# battery.net
KiCad netlist of a schematic drawn in Altium Designer
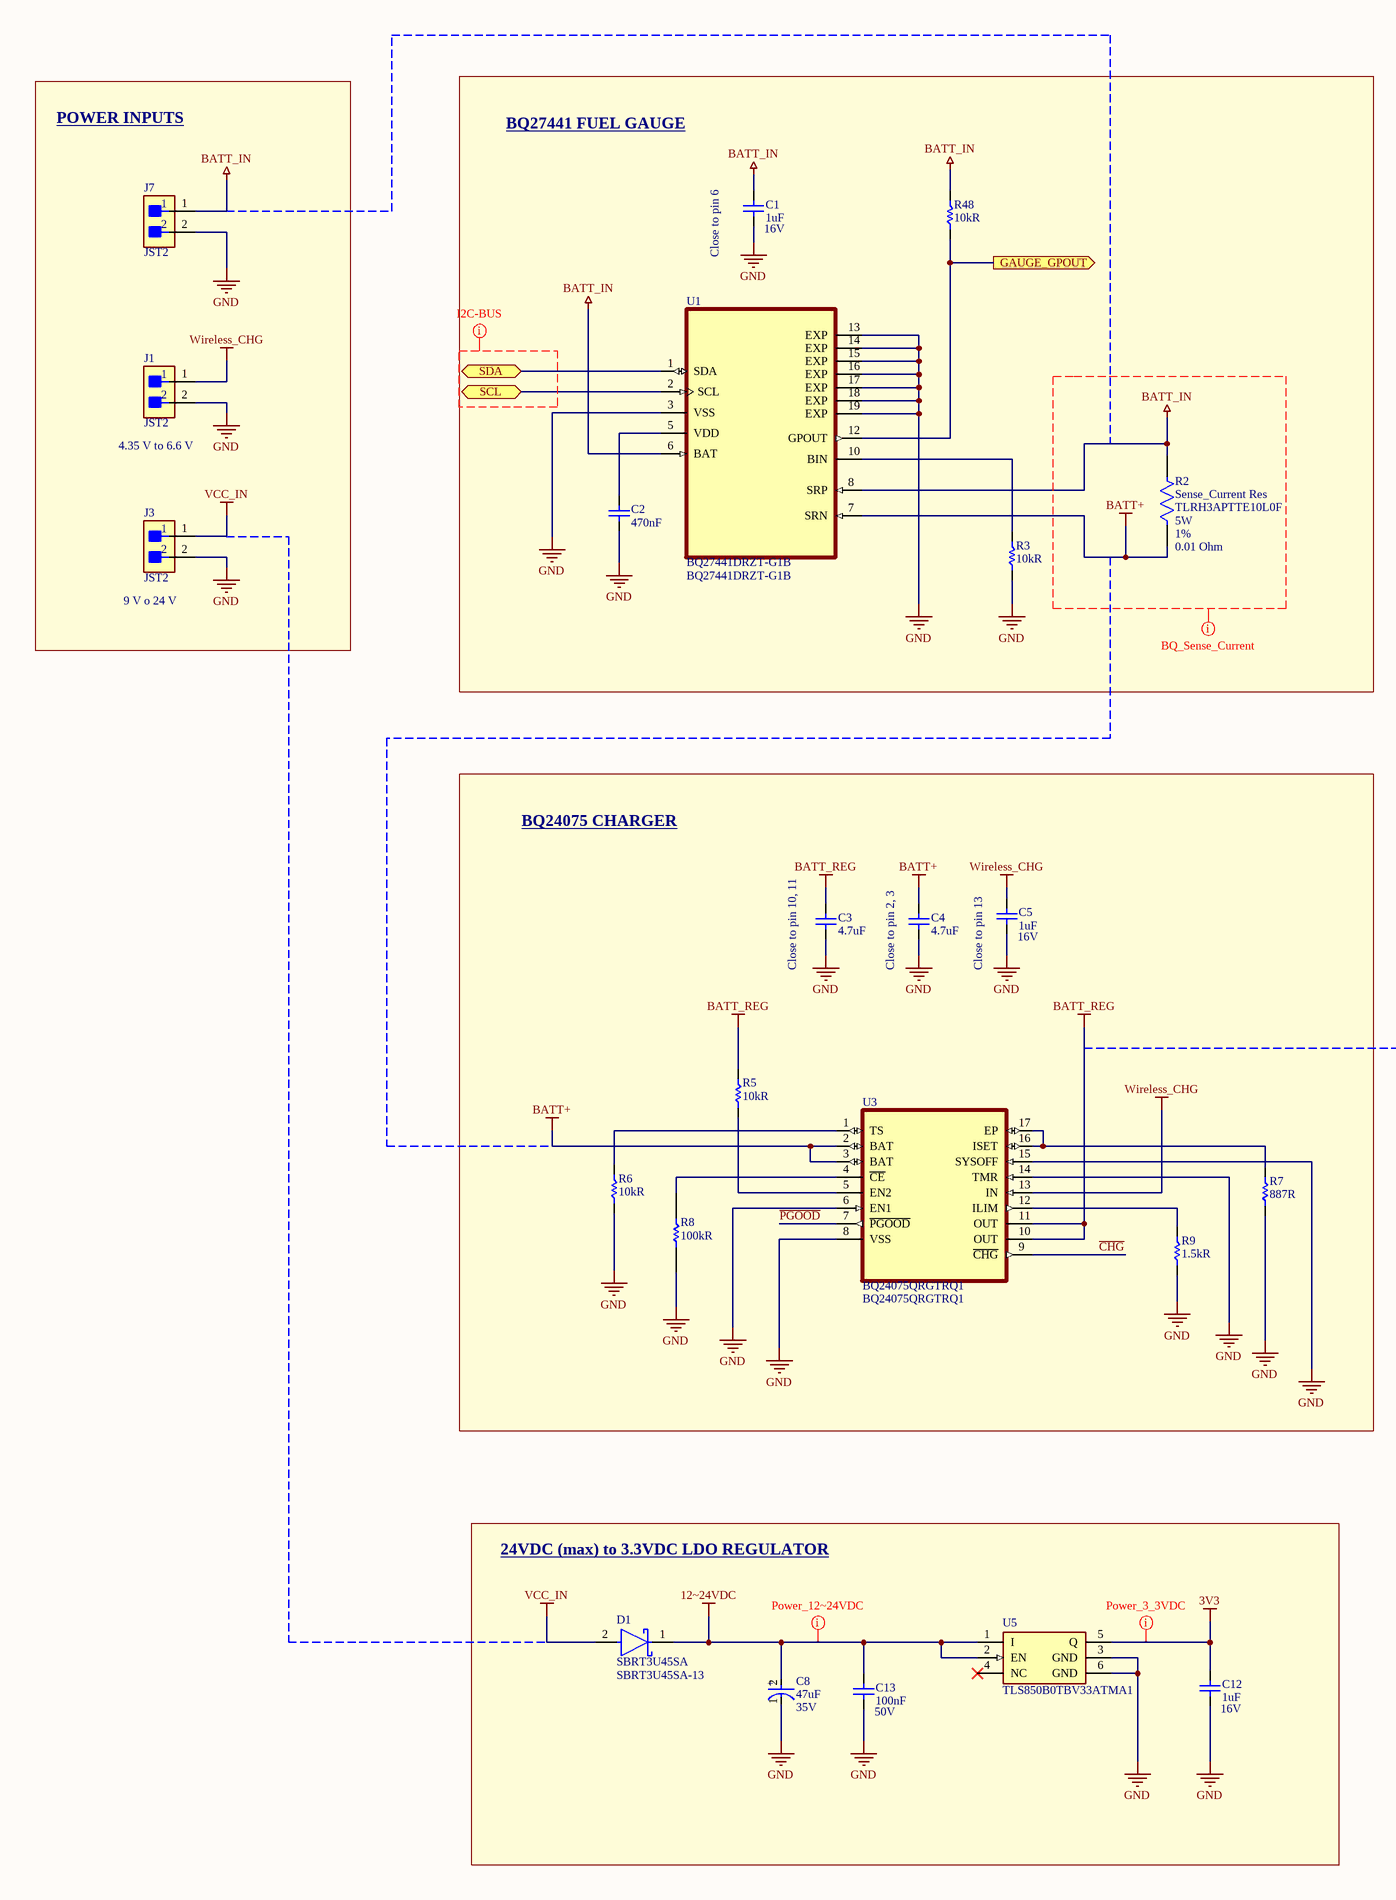
[diagram p0: battery.SchDoc, left]
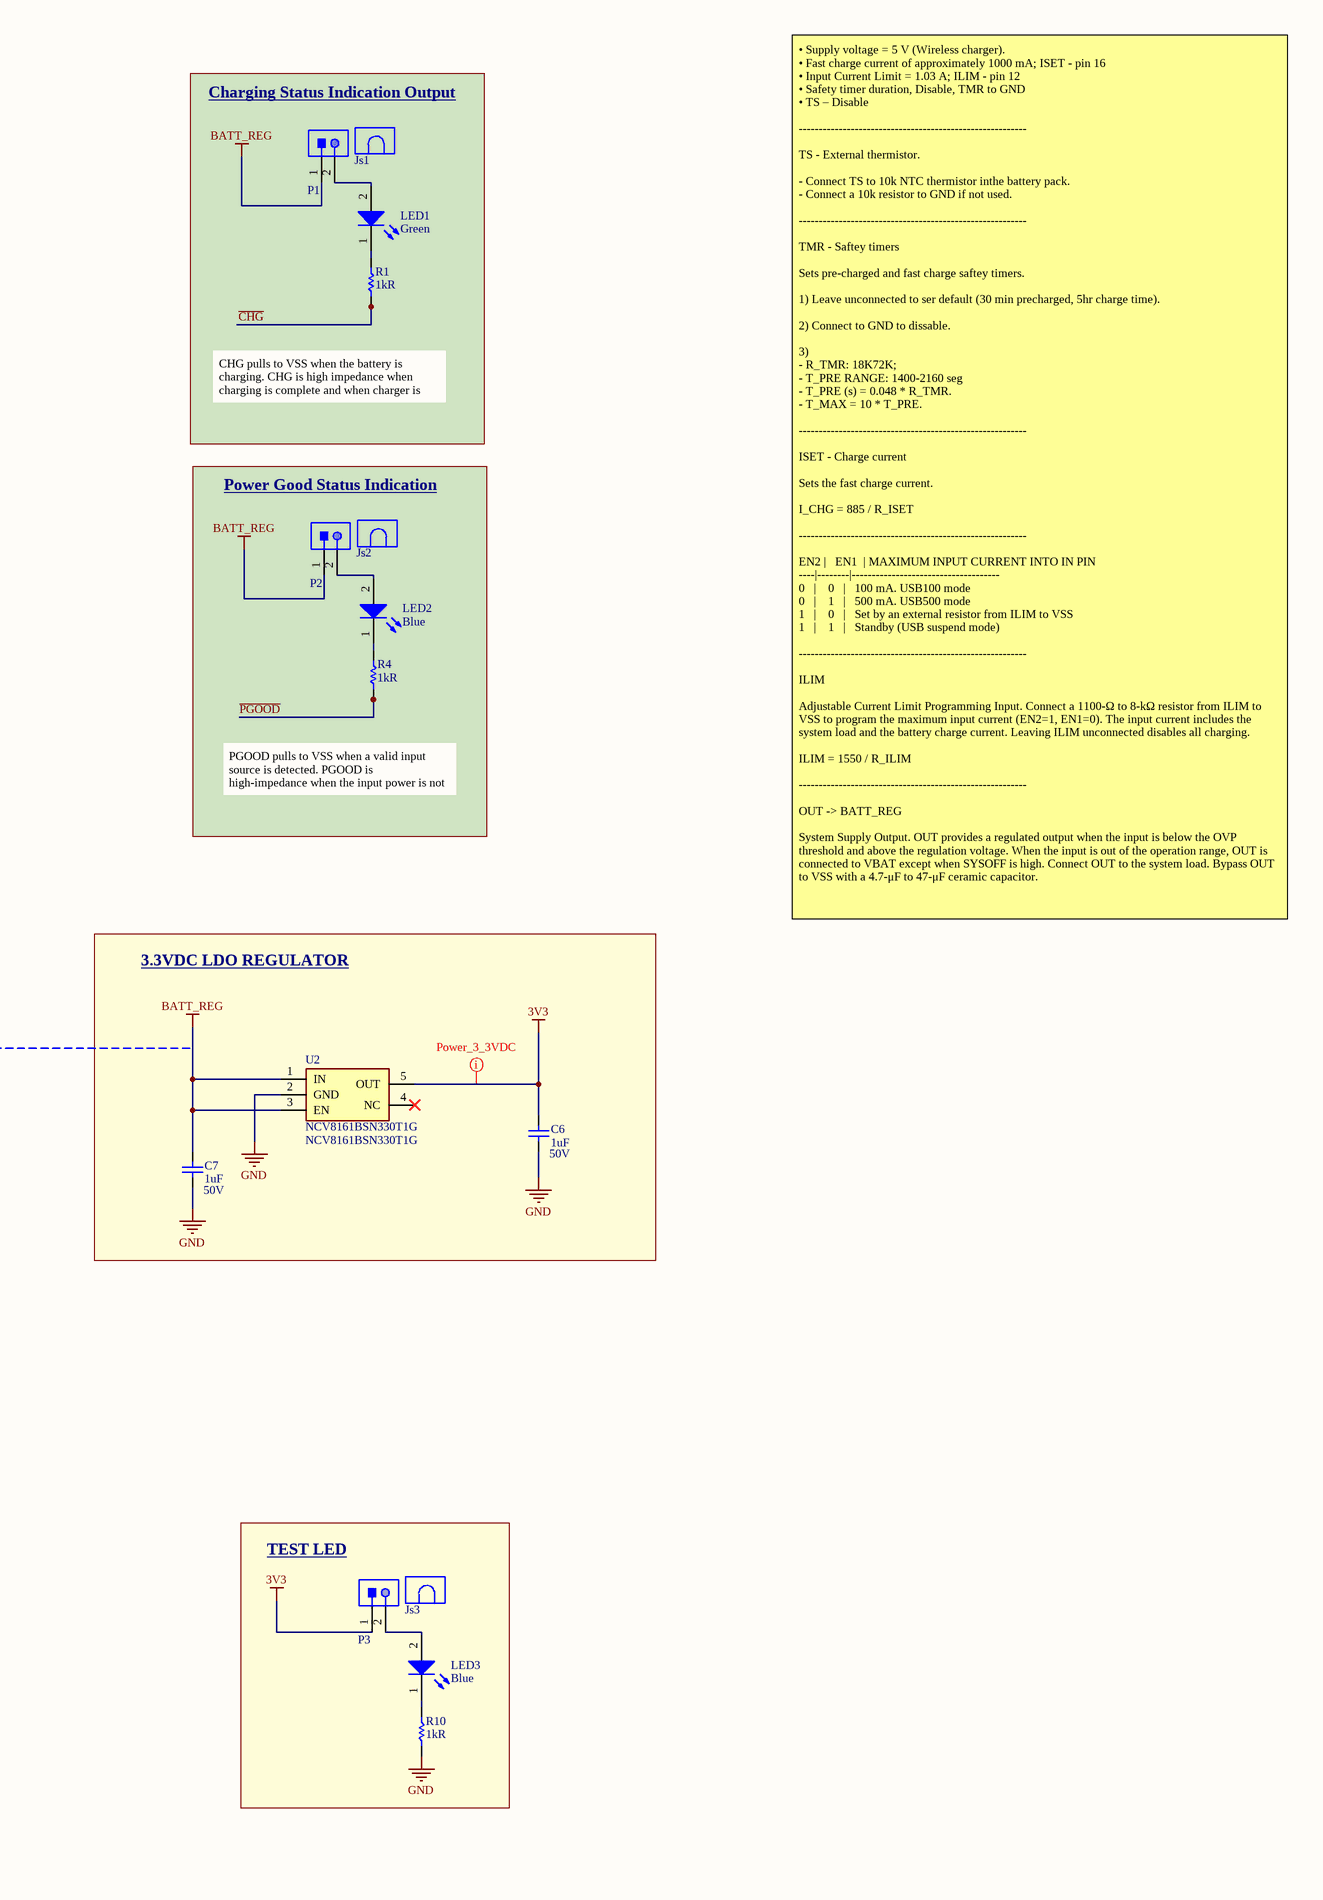
[diagram p1: battery.SchDoc, right]

(export (version "E")
  (design (tool "Eeschema 10.0.6"))
  (components
    (comp (ref "C1")
      (value "1uF")
      (footprint "Cap 0805 (2012 Metric)")
      (description "Ceramic capacitor SMD-0805 1000nF /16V X7R# K +-10%, Samsung, RoHS/3000pcs/")
      (fields
        (field (name "MANUFACTURER") "Samsung")
        (field (name "MANUFACTURER PART NUMBER") "CL21B105KOFNNNG")
        (field (name "VOLTAGE RATING") "16V")
      )
      (libsource (lib "Daniel_Integrated_Library") (part "Capacitor"))
    )
    (comp (ref "C2")
      (value "470nF")
      (footprint "Cap 0805 (2012 Metric)")
      (description "CAP CER 0.47UF 25V X7R 0805")
      (fields
        (field (name "MANUFACTURER") "Samsung")
        (field (name "MANUFACTURER PART NUMBER") "CL21B474KAFNNNE")
      )
      (libsource (lib "Daniel_Integrated_Library") (part "Capacitor"))
    )
    (comp (ref "C3")
      (value "4.7uF")
      (footprint "Cap 0805 (2012 Metric)")
      (fields
        (field (name "MANUFACTURER") "Samsung")
        (field (name "MANUFACTURER PART NUMBER") "CL21A475KAQNNNE")
        (field (name "TOLERANCE") "10%")
      )
      (libsource (lib "Daniel_Integrated_Library") (part "Capacitor"))
    )
    (comp (ref "C4")
      (value "4.7uF")
      (footprint "Cap 0805 (2012 Metric)")
      (fields
        (field (name "MANUFACTURER") "Samsung")
        (field (name "MANUFACTURER PART NUMBER") "CL21A475KAQNNNE")
        (field (name "TOLERANCE") "10%")
      )
      (libsource (lib "Daniel_Integrated_Library") (part "Capacitor"))
    )
    (comp (ref "C5")
      (value "1uF")
      (footprint "Cap 0805 (2012 Metric)")
      (description "Ceramic capacitor SMD-0805 1000nF /16V X7R# K +-10%, Samsung, RoHS/3000pcs/")
      (fields
        (field (name "MANUFACTURER") "Samsung")
        (field (name "MANUFACTURER PART NUMBER") "CL21B105KOFNNNG")
        (field (name "VOLTAGE RATING") "16V")
      )
      (libsource (lib "Daniel_Integrated_Library") (part "Capacitor"))
    )
    (comp (ref "C6")
      (value "1uF")
      (footprint "Cap 0805 (2012 Metric)")
      (description "Cap Ceramic 1uF 50V Y5V -20% to 80% SMD 0805 85C T/R")
      (fields
        (field (name "MANUFACTURER") "Samsung")
        (field (name "MANUFACTURER PART NUMBER") "CL21F105ZBFNNNG")
        (field (name "VOLTAGE RATING") "50V")
      )
      (libsource (lib "Daniel_Integrated_Library") (part "Capacitor"))
    )
    (comp (ref "C7")
      (value "1uF")
      (footprint "Cap 0805 (2012 Metric)")
      (description "Cap Ceramic 1uF 50V Y5V -20% to 80% SMD 0805 85C T/R")
      (fields
        (field (name "MANUFACTURER") "Samsung")
        (field (name "MANUFACTURER PART NUMBER") "CL21F105ZBFNNNG")
        (field (name "VOLTAGE RATING") "50V")
      )
      (libsource (lib "Daniel_Integrated_Library") (part "Capacitor"))
    )
    (comp (ref "C8")
      (value "EEE-FK1V470P")
      (footprint "EEE-FK1V470P")
      (description "Capacitor 47 uF 35 VDC, EEEFK1V470P, Panasonic Automotive & Industrial Systems")
      (fields
        (field (name "MANUFACTURER") "Panasonic")
        (field (name "TOLERANCE") "20%")
        (field (name "CAPACITANCE") "47uF")
        (field (name "VOLTAGE") "35V")
      )
      (libsource (lib "stratos") (part "EEE-FK1V470P"))
    )
    (comp (ref "C12")
      (value "1uF")
      (footprint "Cap 0805 (2012 Metric)")
      (description "Ceramic capacitor SMD-0805 1000nF /16V X7R# K +-10%, Samsung, RoHS/3000pcs/")
      (fields
        (field (name "MANUFACTURER") "Samsung")
        (field (name "MANUFACTURER PART NUMBER") "CL21B105KOFNNNG")
        (field (name "VOLTAGE RATING") "16V")
      )
      (libsource (lib "Daniel_Integrated_Library") (part "Capacitor"))
    )
    (comp (ref "C13")
      (value "100nF")
      (footprint "Cap 0805 (2012 Metric)")
      (fields
        (field (name "MANUFACTURER") "Yageo")
        (field (name "MANUFACTURER PART NUMBER") "CC0805ZRY5V9BB104")
        (field (name "TOLERANCE") "80%")
        (field (name "VOLTAGE RATING") "50V")
      )
      (libsource (lib "Daniel_Integrated_Library") (part "Capacitor"))
    )
    (comp (ref "D1")
      (value "SBRT3U45SA")
      (footprint "SBRT3U45SA-13")
      (description "DIODE SBR 45V 3A SMA")
      (fields
        (field (name "MANUFACTURER") "Diodes")
        (field (name "MANUFACTURER PART NUMBER") "SBRT3U45SA-13")
      )
      (libsource (lib "stratos") (part "SBRT3U45SA"))
    )
    (comp (ref "J1")
      (value "JST2")
      (footprint "JST2")
      (description "Conn Shrouded Header (4 Sides) HDR 2 POS 2.5mm Solder ST Thru-Hole Box")
      (fields
        (field (name "MANUFACTURER") "JST")
        (field (name "MANUFACTURER PART NUMBER") "B2B-XH-A(LF)(SN)")
      )
      (libsource (lib "stratos") (part "JST2"))
    )
    (comp (ref "J3")
      (value "JST2")
      (footprint "JST2")
      (description "Conn Shrouded Header (4 Sides) HDR 2 POS 2.5mm Solder ST Thru-Hole Box")
      (fields
        (field (name "MANUFACTURER") "JST")
        (field (name "MANUFACTURER PART NUMBER") "B2B-XH-A(LF)(SN)")
      )
      (libsource (lib "stratos") (part "JST2"))
    )
    (comp (ref "J7")
      (value "JST2")
      (footprint "JST2")
      (description "Conn Shrouded Header (4 Sides) HDR 2 POS 2.5mm Solder ST Thru-Hole Box")
      (fields
        (field (name "MANUFACTURER") "JST")
        (field (name "MANUFACTURER PART NUMBER") "B2B-XH-A(LF)(SN)")
      )
      (libsource (lib "stratos") (part "JST2"))
    )
    (comp (ref "Js1")
      (value "Jumper (2x1)")
      (footprint "Header JMP 2x1")
      (description "2 (1 x 2) Position Shunt Connector Black Open Top 0.100\" (2.54mm) Gold")
      (fields
        (field (name "MANUFACTURER") "Sullins")
        (field (name "MANUFACTURER PART NUMBER") "QPC02SXGN-RC")
      )
      (libsource (lib "Daniel_Integrated_Library") (part "Jumper (2x1)"))
    )
    (comp (ref "Js2")
      (value "Jumper (2x1)")
      (footprint "Header JMP 2x1")
      (description "2 (1 x 2) Position Shunt Connector Black Open Top 0.100\" (2.54mm) Gold")
      (fields
        (field (name "MANUFACTURER") "Sullins")
        (field (name "MANUFACTURER PART NUMBER") "QPC02SXGN-RC")
      )
      (libsource (lib "Daniel_Integrated_Library") (part "Jumper (2x1)"))
    )
    (comp (ref "Js3")
      (value "Jumper (2x1)")
      (footprint "Header JMP 2x1")
      (description "2 (1 x 2) Position Shunt Connector Black Open Top 0.100\" (2.54mm) Gold")
      (fields
        (field (name "MANUFACTURER") "Sullins")
        (field (name "MANUFACTURER PART NUMBER") "QPC02SXGN-RC")
      )
      (libsource (lib "Daniel_Integrated_Library") (part "Jumper (2x1)"))
    )
    (comp (ref "LED1")
      (value "Green")
      (footprint "LED 0805(2012 METRIC)")
      (description "LED GREEN CLEAR 0805 SMD")
      (fields
        (field (name "MANUFACTURER") "Wurth Electronics")
        (field (name "MANUFACTURER PART NUMBER") "150080VS75000")
      )
      (libsource (lib "Daniel_Integrated_Library") (part "LED"))
    )
    (comp (ref "LED2")
      (value "Blue")
      (footprint "LED 0805(2012 METRIC)")
      (description "SMD LED blue 3.5 V 0805, 150080BS75000, Würth Elektronik")
      (fields
        (field (name "MANUFACTURER") "Wurth Electronics")
        (field (name "MANUFACTURER PART NUMBER") "150080BS75000")
      )
      (libsource (lib "Daniel_Integrated_Library") (part "LED"))
    )
    (comp (ref "LED3")
      (value "Blue")
      (footprint "LED 0805(2012 METRIC)")
      (description "SMD LED blue 3.5 V 0805, 150080BS75000, Würth Elektronik")
      (fields
        (field (name "MANUFACTURER") "Wurth Electronics")
        (field (name "MANUFACTURER PART NUMBER") "150080BS75000")
      )
      (libsource (lib "Daniel_Integrated_Library") (part "LED"))
    )
    (comp (ref "P1")
      (value "Header 2x1")
      (footprint "Header 2x1")
      (description "Connector Header Through Hole 2 position 0.100\" (2.54mm)")
      (fields
        (field (name "MANUFACTURER") "Amphenol FCI")
        (field (name "MANUFACTURER PART NUMBER") "68001-402HLF")
      )
      (libsource (lib "Daniel_Integrated_Library") (part "Header 2x1"))
    )
    (comp (ref "P2")
      (value "Header 2x1")
      (footprint "Header 2x1")
      (description "Connector Header Through Hole 2 position 0.100\" (2.54mm)")
      (fields
        (field (name "MANUFACTURER") "Amphenol FCI")
        (field (name "MANUFACTURER PART NUMBER") "68001-402HLF")
      )
      (libsource (lib "Daniel_Integrated_Library") (part "Header 2x1"))
    )
    (comp (ref "P3")
      (value "Header 2x1")
      (footprint "Header 2x1")
      (description "Connector Header Through Hole 2 position 0.100\" (2.54mm)")
      (fields
        (field (name "MANUFACTURER") "Amphenol FCI")
        (field (name "MANUFACTURER PART NUMBER") "68001-402HLF")
      )
      (libsource (lib "Daniel_Integrated_Library") (part "Header 2x1"))
    )
    (comp (ref "R1")
      (value "1kR")
      (footprint "Res 0805 (2012 Metric)")
      (description "RES 1K OHM 1% 1/4W 0805")
      (fields
        (field (name "MANUFACTURER") "Stackpole Electronics")
        (field (name "MANUFACTURER PART NUMBER") "RNCP0805FTD1K00")
      )
      (libsource (lib "Daniel_Integrated_Library") (part "Resistor"))
    )
    (comp (ref "R2")
      (value "Sense_Current Res")
      (footprint "Sense_Current Res")
      (description "Res Metal Plate 2512 0.01 Ohm 1% 5W ±75ppm/C Pad SMD Automotive T/R")
      (fields
        (field (name "MANUFACTURER") "KOA Speer")
        (field (name "MANUFACTURER PART NUMBER") "TLRH3APTTE10L0F")
        (field (name "POWER") "5W")
        (field (name "TOLERANCE") "1%")
        (field (name "ALTIUM_VALUE") "0.01 Ohm")
      )
      (libsource (lib "stratos") (part "Sense_Current Res"))
    )
    (comp (ref "R3")
      (value "10kR")
      (footprint "Res 0805 (2012 Metric)")
      (description "RES 10K OHM 1% 1/4W 0805")
      (fields
        (field (name "MANUFACTURER") "Stackpole Electronics")
        (field (name "MANUFACTURER PART NUMBER") "RNCP0805FTD10K0")
      )
      (libsource (lib "Daniel_Integrated_Library") (part "Resistor"))
    )
    (comp (ref "R4")
      (value "1kR")
      (footprint "Res 0805 (2012 Metric)")
      (description "RES 1K OHM 1% 1/4W 0805")
      (fields
        (field (name "MANUFACTURER") "Stackpole Electronics")
        (field (name "MANUFACTURER PART NUMBER") "RNCP0805FTD1K00")
      )
      (libsource (lib "Daniel_Integrated_Library") (part "Resistor"))
    )
    (comp (ref "R5")
      (value "10kR")
      (footprint "Res 0805 (2012 Metric)")
      (description "RES 10K OHM 1% 1/4W 0805")
      (fields
        (field (name "MANUFACTURER") "Stackpole Electronics")
        (field (name "MANUFACTURER PART NUMBER") "RNCP0805FTD10K0")
      )
      (libsource (lib "Daniel_Integrated_Library") (part "Resistor"))
    )
    (comp (ref "R6")
      (value "10kR")
      (footprint "Res 0805 (2012 Metric)")
      (description "RES 10K OHM 1% 1/4W 0805")
      (fields
        (field (name "MANUFACTURER") "Stackpole Electronics")
        (field (name "MANUFACTURER PART NUMBER") "RNCP0805FTD10K0")
      )
      (libsource (lib "Daniel_Integrated_Library") (part "Resistor"))
    )
    (comp (ref "R7")
      (value "887R")
      (footprint "Res 0805 (2012 Metric)")
      (description "Res Thick Film 0805 887 Ohm 1% 1/8W 100ppm/C Molded SMD SMD Paper T/R")
      (fields
        (field (name "MANUFACTURER") "Yageo")
        (field (name "MANUFACTURER PART NUMBER") "RC0805FR-07887RL")
      )
      (libsource (lib "Daniel_Integrated_Library") (part "Resistor"))
    )
    (comp (ref "R8")
      (value "100kR")
      (footprint "Res 0805 (2012 Metric)")
      (description "YAGEO         RC0805FR-07100KL            RES, THICK FILM, 100K, 1%, 0.125W, 0805, REEL")
      (fields
        (field (name "MANUFACTURER") "Yageo")
        (field (name "MANUFACTURER PART NUMBER") "RC0805FR-07100KL")
      )
      (libsource (lib "") (part "Resistor_1"))
    )
    (comp (ref "R9")
      (value "1.5kR")
      (footprint "Res 0805 (2012 Metric)")
      (description "Thin Film Resistors 1/10W 1.5Kohm 0.5% 25ppm")
      (fields
        (field (name "MANUFACTURER") "Susumu")
        (field (name "MANUFACTURER PART NUMBER") "RR1220P-152-D")
      )
      (libsource (lib "Daniel_Integrated_Library") (part "Resistor"))
    )
    (comp (ref "R10")
      (value "1kR")
      (footprint "Res 0805 (2012 Metric)")
      (description "RES 1K OHM 1% 1/4W 0805")
      (fields
        (field (name "MANUFACTURER") "Stackpole Electronics")
        (field (name "MANUFACTURER PART NUMBER") "RNCP0805FTD1K00")
      )
      (libsource (lib "Daniel_Integrated_Library") (part "Resistor"))
    )
    (comp (ref "R48")
      (value "10kR")
      (footprint "Res 0805 (2012 Metric)")
      (description "RES 10K OHM 1% 1/4W 0805")
      (fields
        (field (name "MANUFACTURER") "Stackpole Electronics")
        (field (name "MANUFACTURER PART NUMBER") "RNCP0805FTD10K0")
      )
      (libsource (lib "Daniel_Integrated_Library") (part "Resistor"))
    )
    (comp (ref "U1")
      (value "BQ27441DRZT-G1B")
      (footprint "BQ27441DRZT-G1B")
      (fields
        (field (name "MANUFACTURER") "Texas Instruments")
        (field (name "MANUFACTURER PART NUMBER") "BQ27441DRZT-G1B")
      )
      (libsource (lib "stratos") (part "BQ27441DRZT-G1B"))
    )
    (comp (ref "U2")
      (value "NCV8161BSN330T1G")
      (footprint "NCV8161BSN330T1G")
      (description "ON SEMICONDUCTOR - NCV8161BSN330T1G - LDO-FESTSP.REG AEC-Q100 3.3V 0.45A TSOP5")
      (fields
        (field (name "MANUFACTURER") "ON Semiconductor")
        (field (name "MANUFACTURER PART NUMBER") "NCV8161BSN330T1G")
      )
      (libsource (lib "stratos") (part "NCV8161BSN330T1G"))
    )
    (comp (ref "U3")
      (value "BQ24075QRGTRQ1")
      (footprint "BQ24075QRGTRQ1")
      (description "IC BATTERY MGMT LI-ION 16-QFN")
      (fields
        (field (name "MANUFACTURER") "Texas Instruments")
        (field (name "MANUFACTURER PART NUMBER") "BQ24075QRGTRQ1")
      )
      (libsource (lib "stratos") (part "BQ24075QRGTRQ1"))
    )
    (comp (ref "U5")
      (value "TLS850B0TBV33ATMA1")
      (footprint "TLS850B0TBV33ATMA1")
      (description "LDO Regulator Pos 3.3V 0.5A Automotive 6-Pin(5+Tab) TO-263 T/R")
      (fields (field (name "MANUFACTURER") "Infineon"))
      (libsource (lib "stratos") (part "TLS850B0TBV33ATMA1"))
    )
  )
  (nets
    (net (code "1") (name "/GAUGE_GPOUT") (class "Default")
      (node (ref "R48") (pin "2") (pinfunction "2_2") (pintype "passive"))
      (node (ref "U1") (pin "12") (pinfunction "GPOUT_12") (pintype "output"))
    )
    (net (code "2") (name "/SCL") (class "Default")
      (node (ref "U1") (pin "2") (pinfunction "SCL_2") (pintype "input"))
    )
    (net (code "3") (name "/SDA") (class "Default")
      (node (ref "U1") (pin "1") (pinfunction "SDA_1") (pintype "bidirectional"))
    )
    (net (code "4") (name "/~{CHG}") (class "Default")
      (node (ref "R1") (pin "2") (pinfunction "2_2") (pintype "passive"))
      (node (ref "U3") (pin "9") (pinfunction "~{CHG}_9") (pintype "output"))
    )
    (net (code "5") (name "/~{PGOOD}") (class "Default")
      (node (ref "R4") (pin "2") (pinfunction "2_2") (pintype "passive"))
      (node (ref "U3") (pin "7") (pinfunction "~{PGOOD}_7") (pintype "output"))
    )
    (net (code "6") (name "3V3") (class "Default")
      (node (ref "C12") (pin "1") (pinfunction "1_1") (pintype "passive"))
      (node (ref "C6") (pin "1") (pinfunction "1_1") (pintype "passive"))
      (node (ref "P3") (pin "1") (pinfunction "1_1") (pintype "passive"))
      (node (ref "U2") (pin "5") (pinfunction "OUT_5") (pintype "power_in"))
      (node (ref "U5") (pin "5") (pinfunction "Q_5") (pintype "power_in"))
    )
    (net (code "7") (name "12~24VDC") (class "Default")
      (node (ref "C13") (pin "1") (pinfunction "1_1") (pintype "passive"))
      (node (ref "C8") (pin "2") (pinfunction "A_2") (pintype "passive"))
      (node (ref "D1") (pin "1") (pinfunction "C_1") (pintype "passive"))
      (node (ref "U5") (pin "1") (pinfunction "I_1") (pintype "power_in"))
      (node (ref "U5") (pin "2") (pinfunction "EN_2") (pintype "input"))
    )
    (net (code "8") (name "BATT+") (class "Default")
      (node (ref "C4") (pin "1") (pinfunction "1_1") (pintype "passive"))
      (node (ref "R2") (pin "1") (pinfunction "1_1") (pintype "passive"))
      (node (ref "U1") (pin "7") (pinfunction "SRN_7") (pintype "input"))
      (node (ref "U3") (pin "2") (pinfunction "BAT_2") (pintype "bidirectional"))
      (node (ref "U3") (pin "3") (pinfunction "BAT_3") (pintype "bidirectional"))
    )
    (net (code "9") (name "BATT_IN") (class "Default")
      (node (ref "C1") (pin "1") (pinfunction "1_1") (pintype "passive"))
      (node (ref "J7") (pin "1") (pinfunction "1_1") (pintype "power_in"))
      (node (ref "R2") (pin "2") (pinfunction "2_2") (pintype "passive"))
      (node (ref "R48") (pin "1") (pinfunction "1_1") (pintype "passive"))
      (node (ref "U1") (pin "6") (pinfunction "BAT_6") (pintype "input"))
      (node (ref "U1") (pin "8") (pinfunction "SRP_8") (pintype "input"))
    )
    (net (code "10") (name "BATT_REG") (class "Default")
      (node (ref "C3") (pin "1") (pinfunction "1_1") (pintype "passive"))
      (node (ref "C7") (pin "1") (pinfunction "1_1") (pintype "passive"))
      (node (ref "P1") (pin "1") (pinfunction "1_1") (pintype "passive"))
      (node (ref "P2") (pin "1") (pinfunction "1_1") (pintype "passive"))
      (node (ref "R5") (pin "1") (pinfunction "1_1") (pintype "passive"))
      (node (ref "U2") (pin "1") (pinfunction "IN_1") (pintype "power_in"))
      (node (ref "U2") (pin "3") (pinfunction "EN_3") (pintype "power_in"))
      (node (ref "U3") (pin "10") (pinfunction "OUT_10") (pintype "power_in"))
      (node (ref "U3") (pin "11") (pinfunction "OUT_11") (pintype "power_in"))
    )
    (net (code "11") (name "GND") (class "Default")
      (node (ref "C1") (pin "2") (pinfunction "2_2") (pintype "passive"))
      (node (ref "C12") (pin "2") (pinfunction "2_2") (pintype "passive"))
      (node (ref "C13") (pin "2") (pinfunction "2_2") (pintype "passive"))
      (node (ref "C2") (pin "2") (pinfunction "2_2") (pintype "passive"))
      (node (ref "C3") (pin "2") (pinfunction "2_2") (pintype "passive"))
      (node (ref "C4") (pin "2") (pinfunction "2_2") (pintype "passive"))
      (node (ref "C5") (pin "2") (pinfunction "2_2") (pintype "passive"))
      (node (ref "C6") (pin "2") (pinfunction "2_2") (pintype "passive"))
      (node (ref "C7") (pin "2") (pinfunction "2_2") (pintype "passive"))
      (node (ref "C8") (pin "1") (pinfunction "C_1") (pintype "passive"))
      (node (ref "J1") (pin "2") (pinfunction "2_2") (pintype "passive"))
      (node (ref "J3") (pin "2") (pinfunction "2_2") (pintype "passive"))
      (node (ref "J7") (pin "2") (pinfunction "2_2") (pintype "passive"))
      (node (ref "R10") (pin "2") (pinfunction "2_2") (pintype "passive"))
      (node (ref "R3") (pin "2") (pinfunction "2_2") (pintype "passive"))
      (node (ref "R6") (pin "2") (pinfunction "2_2") (pintype "passive"))
      (node (ref "R7") (pin "2") (pinfunction "2_2") (pintype "passive"))
      (node (ref "R8") (pin "2") (pinfunction "2_2") (pintype "passive"))
      (node (ref "R9") (pin "2") (pinfunction "2_2") (pintype "passive"))
      (node (ref "U1") (pin "13") (pinfunction "EXP_13") (pintype "power_in"))
      (node (ref "U1") (pin "14") (pinfunction "EXP_14") (pintype "power_in"))
      (node (ref "U1") (pin "15") (pinfunction "EXP_15") (pintype "power_in"))
      (node (ref "U1") (pin "16") (pinfunction "EXP_16") (pintype "power_in"))
      (node (ref "U1") (pin "17") (pinfunction "EXP_17") (pintype "power_in"))
      (node (ref "U1") (pin "18") (pinfunction "EXP_18") (pintype "power_in"))
      (node (ref "U1") (pin "19") (pinfunction "EXP_19") (pintype "power_in"))
      (node (ref "U1") (pin "3") (pinfunction "VSS_3") (pintype "power_in"))
      (node (ref "U2") (pin "2") (pinfunction "GND_2") (pintype "passive"))
      (node (ref "U3") (pin "14") (pinfunction "TMR_14") (pintype "input"))
      (node (ref "U3") (pin "15") (pinfunction "SYSOFF_15") (pintype "input"))
      (node (ref "U3") (pin "6") (pinfunction "EN1_6") (pintype "input"))
      (node (ref "U3") (pin "8") (pinfunction "VSS_8") (pintype "power_in"))
      (node (ref "U5") (pin "3") (pinfunction "GND_3") (pintype "power_in"))
      (node (ref "U5") (pin "6") (pinfunction "GND_6") (pintype "power_in"))
    )
    (net (code "12") (name "Net-(LED1-A)") (class "Default")
      (node (ref "LED1") (pin "2") (pinfunction "A_2") (pintype "passive"))
      (node (ref "P1") (pin "2") (pinfunction "2_2") (pintype "passive"))
    )
    (net (code "13") (name "Net-(LED1-K)") (class "Default")
      (node (ref "LED1") (pin "1") (pinfunction "K_1") (pintype "passive"))
      (node (ref "R1") (pin "1") (pinfunction "1_1") (pintype "passive"))
    )
    (net (code "14") (name "Net-(LED2-A)") (class "Default")
      (node (ref "LED2") (pin "2") (pinfunction "A_2") (pintype "passive"))
      (node (ref "P2") (pin "2") (pinfunction "2_2") (pintype "passive"))
    )
    (net (code "15") (name "Net-(LED2-K)") (class "Default")
      (node (ref "LED2") (pin "1") (pinfunction "K_1") (pintype "passive"))
      (node (ref "R4") (pin "1") (pinfunction "1_1") (pintype "passive"))
    )
    (net (code "16") (name "Net-(LED3-A)") (class "Default")
      (node (ref "LED3") (pin "2") (pinfunction "A_2") (pintype "passive"))
      (node (ref "P3") (pin "2") (pinfunction "2_2") (pintype "passive"))
    )
    (net (code "17") (name "Net-(LED3-K)") (class "Default")
      (node (ref "LED3") (pin "1") (pinfunction "K_1") (pintype "passive"))
      (node (ref "R10") (pin "1") (pinfunction "1_1") (pintype "passive"))
    )
    (net (code "18") (name "Net-(U1-BIN)") (class "Default")
      (node (ref "R3") (pin "1") (pinfunction "1_1") (pintype "passive"))
      (node (ref "U1") (pin "10") (pinfunction "BIN_10") (pintype "passive"))
    )
    (net (code "19") (name "Net-(U1-VDD)") (class "Default")
      (node (ref "C2") (pin "1") (pinfunction "1_1") (pintype "passive"))
      (node (ref "U1") (pin "5") (pinfunction "VDD_5") (pintype "power_in"))
    )
    (net (code "20") (name "Net-(U3-EN2)") (class "Default")
      (node (ref "R5") (pin "2") (pinfunction "2_2") (pintype "passive"))
      (node (ref "U3") (pin "5") (pinfunction "EN2_5") (pintype "passive"))
    )
    (net (code "21") (name "Net-(U3-EP)") (class "Default")
      (node (ref "R7") (pin "1") (pinfunction "1_1") (pintype "passive"))
      (node (ref "U3") (pin "16") (pinfunction "ISET_16") (pintype "bidirectional"))
      (node (ref "U3") (pin "17") (pinfunction "EP_17") (pintype "bidirectional"))
    )
    (net (code "22") (name "Net-(U3-ILIM)") (class "Default")
      (node (ref "R9") (pin "1") (pinfunction "1_1") (pintype "passive"))
      (node (ref "U3") (pin "12") (pinfunction "ILIM_12") (pintype "output"))
    )
    (net (code "23") (name "Net-(U3-TS)") (class "Default")
      (node (ref "R6") (pin "1") (pinfunction "1_1") (pintype "passive"))
      (node (ref "U3") (pin "1") (pinfunction "TS_1") (pintype "bidirectional"))
    )
    (net (code "24") (name "Net-(U3-~{CE})") (class "Default")
      (node (ref "R8") (pin "1") (pinfunction "1_1") (pintype "passive"))
      (node (ref "U3") (pin "4") (pinfunction "~{CE}_4") (pintype "passive"))
    )
    (net (code "25") (name "VCC_IN") (class "Default")
      (node (ref "D1") (pin "2") (pinfunction "A_2") (pintype "passive"))
      (node (ref "J3") (pin "1") (pinfunction "1_1") (pintype "power_in"))
    )
    (net (code "26") (name "Wireless_CHG") (class "Default")
      (node (ref "C5") (pin "1") (pinfunction "1_1") (pintype "passive"))
      (node (ref "J1") (pin "1") (pinfunction "1_1") (pintype "power_in"))
      (node (ref "U3") (pin "13") (pinfunction "IN_13") (pintype "input"))
    )
    (net (code "27") (name "unconnected-(U2-NC-Pad4)") (class "Default")
      (node (ref "U2") (pin "4") (pinfunction "NC_4") (pintype "passive+no_connect"))
    )
    (net (code "28") (name "unconnected-(U5-NC-Pad4)") (class "Default")
      (node (ref "U5") (pin "4") (pinfunction "NC_4") (pintype "passive+no_connect"))
    )
  )
)
